# flux1_1.net
KiCad netlist of a schematic drawn in EAGLE
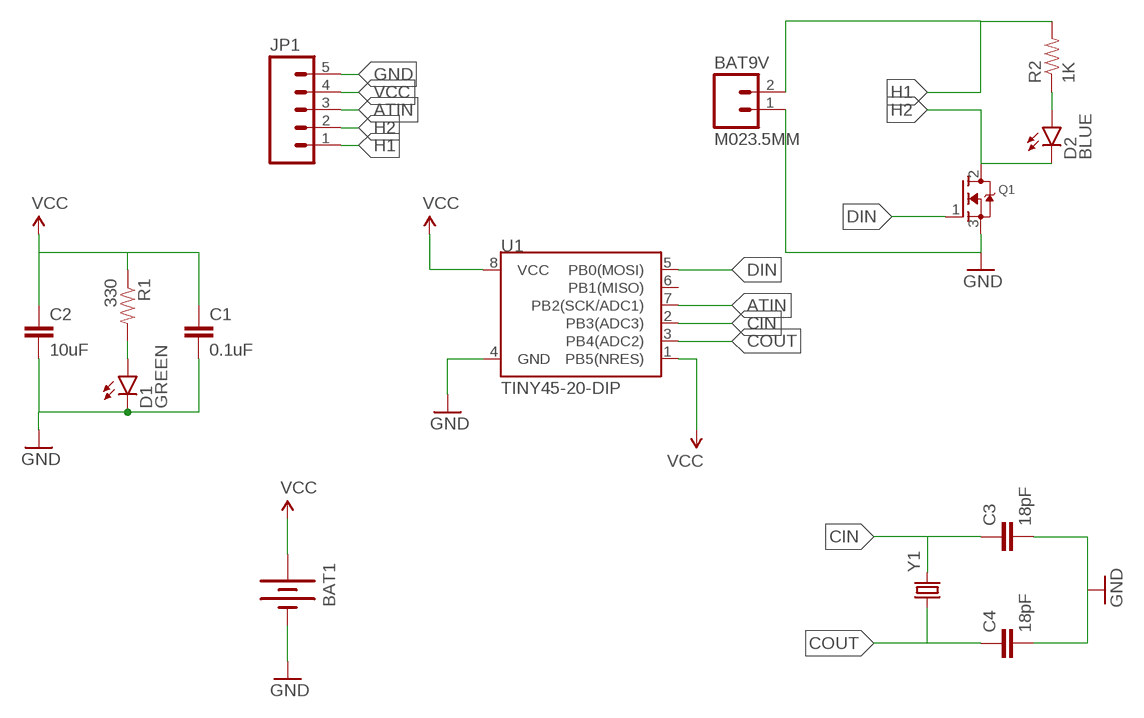
[diagram p0: schematic, sheet 1]

(export (version "E")
  (design (tool "Eeschema 10.0.6"))
  (components
    (comp (ref "BAT1")
      (value "BATTERY12MM")
      (footprint "eagle-import:BATTCON_12MM")
      (libsource (lib "eagle-import") (part "BATTERY12MM"))
    )
    (comp (ref "BAT9V")
      (value "M023.5MM")
      (footprint "eagle-import:SCREWTERMINAL-3.5MM-2")
      (libsource (lib "eagle-import") (part "M023.5MM"))
    )
    (comp (ref "C1")
      (value "0.1uF")
      (footprint "eagle-import:0603-CAP")
      (libsource (lib "eagle-import") (part "0.1UF-25V(+80/-20%)(0603)"))
    )
    (comp (ref "C2")
      (value "10uF")
      (footprint "eagle-import:0603-CAP")
      (libsource (lib "eagle-import") (part "10UF-6.3V-20%(0603)"))
    )
    (comp (ref "C3")
      (value "18pF")
      (footprint "eagle-import:0603-CAP")
      (libsource (lib "eagle-import") (part "18PF-50V-5%(0603)"))
    )
    (comp (ref "C4")
      (value "18pF")
      (footprint "eagle-import:0603-CAP")
      (libsource (lib "eagle-import") (part "18PF-50V-5%(0603)"))
    )
    (comp (ref "D1")
      (value "GREEN")
      (footprint "eagle-import:LED-0603")
      (libsource (lib "eagle-import") (part "LED-GREEN0603"))
    )
    (comp (ref "D2")
      (value "BLUE")
      (footprint "eagle-import:LED-0603")
      (libsource (lib "eagle-import") (part "LED-BLUE0603"))
    )
    (comp (ref "JP1")
      (value "M05SMD")
      (footprint "eagle-import:1X05-1MM")
      (libsource (lib "eagle-import") (part "M05SMD"))
    )
    (comp (ref "Q1")
      (value "MOSFET-NGDS_TO220V")
      (footprint "eagle-import:TO220V")
      (libsource (lib "eagle-import") (part "MOSFET-NGDS_TO220V"))
    )
    (comp (ref "R1")
      (value "330")
      (footprint "eagle-import:0603-RES")
      (libsource (lib "eagle-import") (part "330OHM1/10W1%(0603)"))
    )
    (comp (ref "R2")
      (value "1K")
      (footprint "eagle-import:0603-RES")
      (libsource (lib "eagle-import") (part "1KOHM1/10W1%(0603)"))
    )
    (comp (ref "U1")
      (value "TINY45-20-DIP")
      (footprint "eagle-import:DIP08")
      (libsource (lib "eagle-import") (part "ATTINY45TINY45-20-DIP"))
    )
    (comp (ref "Y1")
      (value "CRYSTALHC49US")
      (footprint "eagle-import:HC49US")
      (libsource (lib "eagle-import") (part "CRYSTALHC49US"))
    )
  )
  (nets
    (net (code "1") (name "ATIN") (class "Default")
      (node (ref "JP1") (pin "3") (pinfunction "3_3") (pintype "passive"))
      (node (ref "U1") (pin "7") (pinfunction "PB2(SCK/ADC1)_7") (pintype "bidirectional"))
    )
    (net (code "2") (name "CIN") (class "Default")
      (node (ref "C3") (pin "1") (pinfunction "1_1") (pintype "passive"))
      (node (ref "U1") (pin "2") (pinfunction "PB3(ADC3)_2") (pintype "bidirectional"))
      (node (ref "Y1") (pin "2") (pinfunction "2_2") (pintype "passive"))
    )
    (net (code "3") (name "COUT") (class "Default")
      (node (ref "C4") (pin "1") (pinfunction "1_1") (pintype "passive"))
      (node (ref "U1") (pin "3") (pinfunction "PB4(ADC2)_3") (pintype "bidirectional"))
      (node (ref "Y1") (pin "1") (pinfunction "1_1") (pintype "passive"))
    )
    (net (code "4") (name "DIN") (class "Default")
      (node (ref "Q1") (pin "1") (pinfunction "G_1") (pintype "bidirectional"))
      (node (ref "U1") (pin "5") (pinfunction "PB0(MOSI)_5") (pintype "bidirectional"))
    )
    (net (code "5") (name "GND") (class "Default")
      (node (ref "BAT1") (pin "GND") (pinfunction "-_GND") (pintype "power_in"))
      (node (ref "BAT9V") (pin "1") (pinfunction "1_1") (pintype "passive"))
      (node (ref "C1") (pin "2") (pinfunction "2_2") (pintype "passive"))
      (node (ref "C2") (pin "2") (pinfunction "2_2") (pintype "passive"))
      (node (ref "C3") (pin "2") (pinfunction "2_2") (pintype "passive"))
      (node (ref "C4") (pin "2") (pinfunction "2_2") (pintype "passive"))
      (node (ref "D1") (pin "C") (pinfunction "C_C") (pintype "passive"))
      (node (ref "JP1") (pin "5") (pinfunction "5_5") (pintype "passive"))
      (node (ref "Q1") (pin "3") (pinfunction "S_3") (pintype "bidirectional"))
      (node (ref "U1") (pin "4") (pinfunction "GND_4") (pintype "bidirectional"))
    )
    (net (code "6") (name "H1") (class "Default")
      (node (ref "BAT9V") (pin "2") (pinfunction "2_2") (pintype "passive"))
      (node (ref "JP1") (pin "1") (pinfunction "1_1") (pintype "passive"))
      (node (ref "R2") (pin "2") (pinfunction "2_2") (pintype "passive"))
    )
    (net (code "7") (name "H2") (class "Default")
      (node (ref "D2") (pin "C") (pinfunction "C_C") (pintype "passive"))
      (node (ref "JP1") (pin "2") (pinfunction "2_2") (pintype "passive"))
      (node (ref "Q1") (pin "2") (pinfunction "D_2") (pintype "bidirectional"))
    )
    (net (code "8") (name "Net-(D1-PadA)") (class "Default")
      (node (ref "D1") (pin "A") (pinfunction "A_A") (pintype "passive"))
      (node (ref "R1") (pin "2") (pinfunction "2_2") (pintype "passive"))
    )
    (net (code "9") (name "Net-(D2-PadA)") (class "Default")
      (node (ref "D2") (pin "A") (pinfunction "A_A") (pintype "passive"))
      (node (ref "R2") (pin "1") (pinfunction "1_1") (pintype "passive"))
    )
    (net (code "10") (name "VCC") (class "Default")
      (node (ref "BAT1") (pin "PWR@1") (pinfunction "+_PWR@1") (pintype "power_in"))
      (node (ref "C1") (pin "1") (pinfunction "1_1") (pintype "passive"))
      (node (ref "C2") (pin "1") (pinfunction "1_1") (pintype "passive"))
      (node (ref "JP1") (pin "4") (pinfunction "4_4") (pintype "passive"))
      (node (ref "R1") (pin "1") (pinfunction "1_1") (pintype "passive"))
      (node (ref "U1") (pin "1") (pinfunction "PB5(NRES)_1") (pintype "bidirectional"))
      (node (ref "U1") (pin "8") (pinfunction "VCC_8") (pintype "bidirectional"))
    )
    (net (code "11") (name "unconnected-(U1-PB1(MISO)-Pad6)") (class "Default")
      (node (ref "U1") (pin "6") (pinfunction "PB1(MISO)_6") (pintype "bidirectional"))
    )
  )
)
